# Driveunit_RS485_Topsheet.net
KiCad netlist of a schematic drawn in Altium Designer
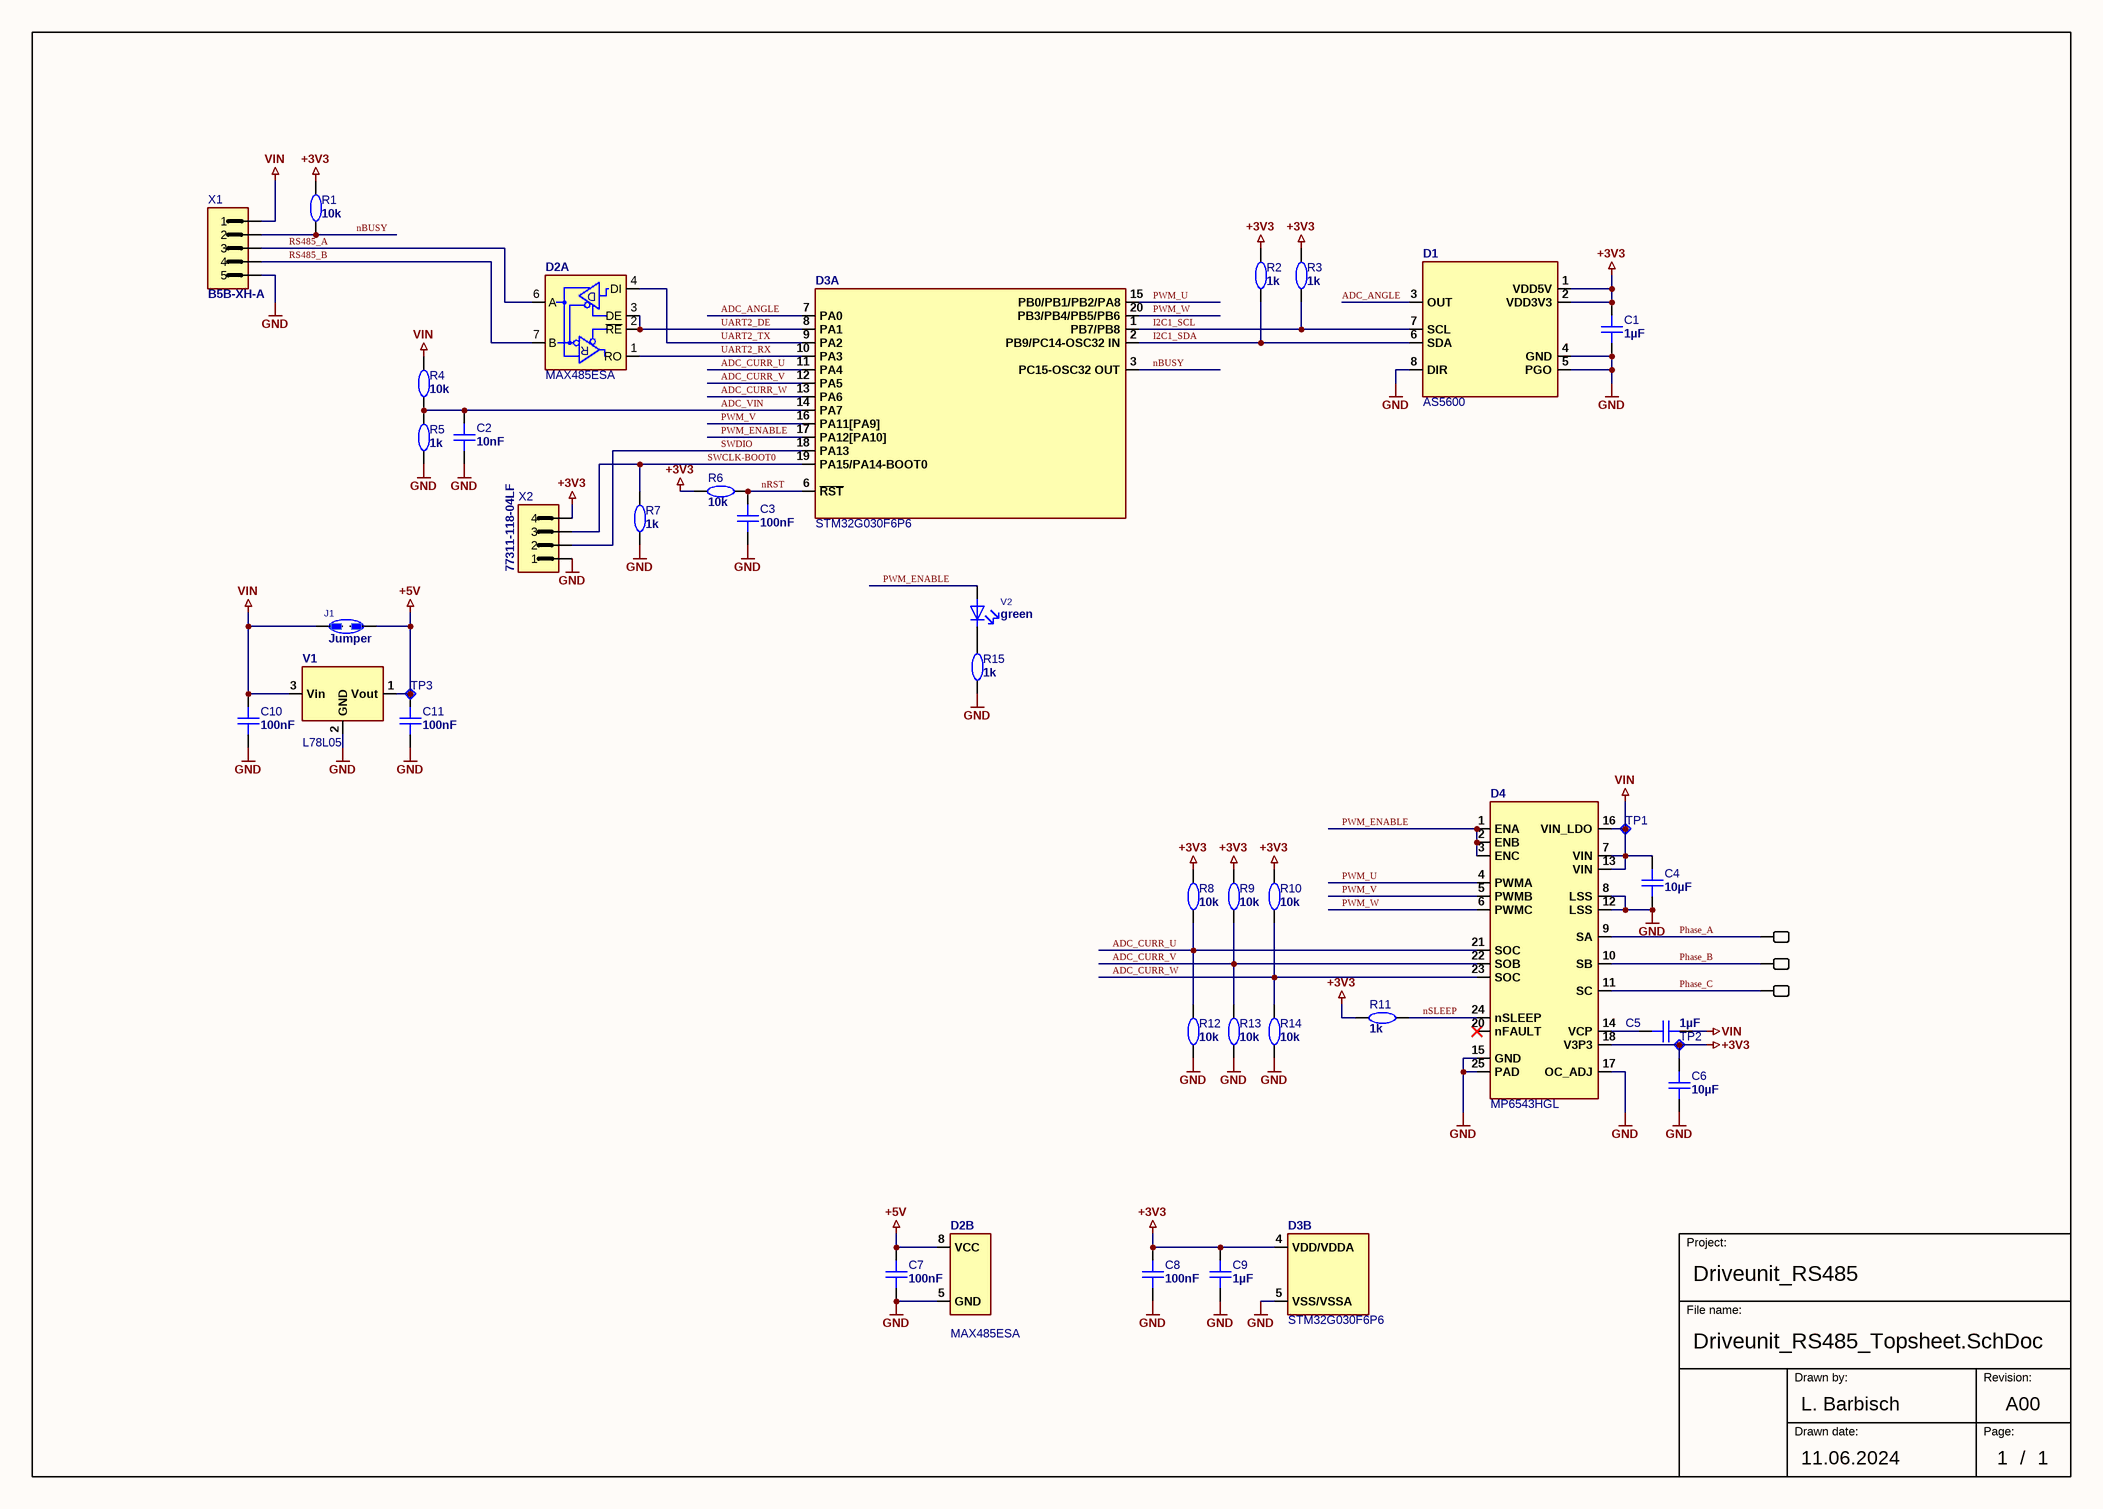
[diagram p0: Driveunit_RS485_Topsheet.SchDoc]

(export (version "E")
  (design (tool "Eeschema 10.0.6"))
  (components
    (comp (ref "C1")
      (value "1µF")
      (footprint "C-0603_1608_095_L_RF")
      (description "Cap Cer SMD 1u 16V 10% 0603 X7R")
      (fields
        (field (name "MANUFACTURER PART NUMBER") "0603YC105KAT2A")
        (field (name "MANUFACTURER") "AVX")
        (field (name "USER") "epph")
      )
      (libsource (lib "GPV Switzerland SA") (part "CAP"))
    )
    (comp (ref "C2")
      (value "10nF")
      (footprint "C-0603_1608_095_L_RF")
      (description "Cap Cer SMD 10n 50V 10% 0603 X7R")
      (fields
        (field (name "MANUFACTURER") "AVX")
        (field (name "MANUFACTURER PART NUMBER") "06035C103KAT")
        (field (name "USER") "epph")
      )
      (libsource (lib "GPV Switzerland SA") (part "CAP"))
    )
    (comp (ref "C3")
      (value "100nF")
      (footprint "C-0603_1608_095_L_RF")
      (description "Cap Cer SMD 100n 100V 10% 0603 X7R")
      (fields
        (field (name "MANUFACTURER PART NUMBER") "GRM188R72A104KA35")
        (field (name "MANUFACTURER") "MURATA")
        (field (name "USER") "zupa")
      )
      (libsource (lib "GPV Switzerland SA") (part "CAP"))
    )
    (comp (ref "C4")
      (value "10µF")
      (footprint "C-1210_3225_230_L_RF")
      (description "CAP CER 10uF 50V X7S 1210")
      (fields
        (field (name "MANUFACTURER") "TDK")
        (field (name "MANUFACTURER PART NUMBER") "C3225X7S1H106K250AE")
        (field (name "USER") "zupa")
      )
      (libsource (lib "GPV Switzerland SA") (part "CAP"))
    )
    (comp (ref "C5")
      (value "1µF")
      (footprint "C-0603_1608_095_L_RF")
      (description "Cap Cer SMD 1u 16V 10% 0603 X7R")
      (fields
        (field (name "MANUFACTURER PART NUMBER") "0603YC105KAT2A")
        (field (name "MANUFACTURER") "AVX")
        (field (name "USER") "epph")
      )
      (libsource (lib "GPV Switzerland SA") (part "CAP"))
    )
    (comp (ref "C6")
      (value "10µF")
      (footprint "C-0805_2012_145_L_RF")
      (description "Cap Cer SMD 10u 16V 10% 0805 X5R")
      (fields
        (field (name "MANUFACTURER PART NUMBER") "0805YD106KAT2A")
        (field (name "MANUFACTURER") "AVX")
        (field (name "USER") "zupa")
      )
      (libsource (lib "GPV Switzerland SA") (part "CAP"))
    )
    (comp (ref "C7")
      (value "100nF")
      (footprint "C-0603_1608_095_L_RF")
      (description "Cap Cer SMD 100n 100V 10% 0603 X7R")
      (fields
        (field (name "MANUFACTURER PART NUMBER") "GRM188R72A104KA35")
        (field (name "MANUFACTURER") "MURATA")
        (field (name "USER") "zupa")
      )
      (libsource (lib "GPV Switzerland SA") (part "CAP"))
    )
    (comp (ref "C8")
      (value "100nF")
      (footprint "C-0603_1608_095_L_RF")
      (description "Cap Cer SMD 100n 100V 10% 0603 X7R")
      (fields
        (field (name "MANUFACTURER PART NUMBER") "GRM188R72A104KA35")
        (field (name "MANUFACTURER") "MURATA")
        (field (name "USER") "zupa")
      )
      (libsource (lib "GPV Switzerland SA") (part "CAP"))
    )
    (comp (ref "C9")
      (value "1µF")
      (footprint "C-0603_1608_095_L_RF")
      (description "Cap Cer SMD 1u 16V 10% 0603 X7R")
      (fields
        (field (name "MANUFACTURER PART NUMBER") "0603YC105KAT2A")
        (field (name "MANUFACTURER") "AVX")
        (field (name "USER") "epph")
      )
      (libsource (lib "GPV Switzerland SA") (part "CAP"))
    )
    (comp (ref "C10")
      (value "100nF")
      (footprint "C-0603_1608_095_L_RF")
      (description "Cap Cer SMD 100n 100V 10% 0603 X7R")
      (fields
        (field (name "MANUFACTURER PART NUMBER") "GRM188R72A104KA35")
        (field (name "MANUFACTURER") "MURATA")
        (field (name "USER") "zupa")
      )
      (libsource (lib "GPV Switzerland SA") (part "CAP"))
    )
    (comp (ref "C11")
      (value "100nF")
      (footprint "C-0603_1608_095_L_RF")
      (description "Cap Cer SMD 100n 100V 10% 0603 X7R")
      (fields
        (field (name "MANUFACTURER PART NUMBER") "GRM188R72A104KA35")
        (field (name "MANUFACTURER") "MURATA")
        (field (name "USER") "zupa")
      )
      (libsource (lib "GPV Switzerland SA") (part "CAP"))
    )
    (comp (ref "D1")
      (value "AS5600")
      (footprint "SOIC8_N_RF")
      (description "IC Sensor Rotation Magnet 12bit")
      (fields (field (name "MANUFACTURER") "AMS"))
      (libsource (lib "Global Library") (part "AS5600"))
    )
    (comp (ref "D2")
      (value "MAX485ESA")
      (footprint "SOIC8_N_RF")
      (description "IC Transceiver RS485 5V")
      (fields (field (name "MANUFACTURER") "Maxim"))
      (libsource (lib "") (part "MAX485ESA_1"))
    )
    (comp (ref "D3")
      (value "STM32G030F6P6")
      (footprint "TSSOP20_N_RF")
      (description "IC MCU Cortex M0+ 32K Flash, 8K RAM, 64MHz")
      (fields (field (name "MANUFACTURER") "ST"))
      (libsource (lib "Global Library") (part "STM32G030F6P6"))
    )
    (comp (ref "D4")
      (value "MP6543HGL")
      (footprint "QFN24_5x7_N_RF")
      (description "Motor Driver 3-Phase 3-22V 2A")
      (fields
        (field (name "MANUFACTURER") "Monolithic Power Systems")
        (field (name "MANUFACTURER PART NUMBER") "MP6543HGL-A-P")
      )
      (libsource (lib "Global Library") (part "MP6543HGL-A-P"))
    )
    (comp (ref "J1")
      (value "Jumper")
      (footprint "J-1206_Solderjumper_2Pin")
      (description "Solder jumper 2Pin")
      (fields (field (name "USER") "epph"))
      (libsource (lib "GPV Switzerland SA") (part "Solder jumper 2Pin"))
    )
    (comp (ref "R1")
      (value "10k")
      (footprint "R-0603_1608_050_L_RF")
      (description "Res SMD 10k 1% 0.1W 0603")
      (fields
        (field (name "MANUFACTURER") "YAGEO")
        (field (name "MANUFACTURER PART NUMBER") "RC0603FR-0710KL")
        (field (name "USER") "zupa")
      )
      (libsource (lib "GPV Switzerland SA") (part "RES"))
    )
    (comp (ref "R2")
      (value "1k")
      (footprint "R-0603_1608_050_L_RF")
      (description "Res SMD 1k 1% 0.1W 0603")
      (fields
        (field (name "MANUFACTURER") "YAGEO")
        (field (name "MANUFACTURER PART NUMBER") "RC0603FR-071KL")
        (field (name "USER") "zupa")
      )
      (libsource (lib "GPV Switzerland SA") (part "RES"))
    )
    (comp (ref "R3")
      (value "1k")
      (footprint "R-0603_1608_050_L_RF")
      (description "Res SMD 1k 1% 0.1W 0603")
      (fields
        (field (name "MANUFACTURER") "YAGEO")
        (field (name "MANUFACTURER PART NUMBER") "RC0603FR-071KL")
        (field (name "USER") "zupa")
      )
      (libsource (lib "GPV Switzerland SA") (part "RES"))
    )
    (comp (ref "R4")
      (value "10k")
      (footprint "R-0603_1608_050_L_RF")
      (description "Res SMD 10k 1% 0.1W 0603")
      (fields
        (field (name "MANUFACTURER") "YAGEO")
        (field (name "MANUFACTURER PART NUMBER") "RC0603FR-0710KL")
        (field (name "USER") "zupa")
      )
      (libsource (lib "GPV Switzerland SA") (part "RES"))
    )
    (comp (ref "R5")
      (value "1k")
      (footprint "R-0603_1608_050_L_RF")
      (description "Res SMD 1k 1% 0.1W 0603")
      (fields
        (field (name "MANUFACTURER") "YAGEO")
        (field (name "MANUFACTURER PART NUMBER") "RC0603FR-071KL")
        (field (name "USER") "zupa")
      )
      (libsource (lib "GPV Switzerland SA") (part "RES"))
    )
    (comp (ref "R6")
      (value "10k")
      (footprint "R-0603_1608_050_L_RF")
      (description "Res SMD 10k 1% 0.1W 0603")
      (fields
        (field (name "MANUFACTURER") "YAGEO")
        (field (name "MANUFACTURER PART NUMBER") "RC0603FR-0710KL")
        (field (name "USER") "zupa")
      )
      (libsource (lib "GPV Switzerland SA") (part "RES"))
    )
    (comp (ref "R7")
      (value "1k")
      (footprint "R-0603_1608_050_L_RF")
      (description "Res SMD 1k 1% 0.1W 0603")
      (fields
        (field (name "MANUFACTURER") "YAGEO")
        (field (name "MANUFACTURER PART NUMBER") "RC0603FR-071KL")
        (field (name "USER") "zupa")
      )
      (libsource (lib "GPV Switzerland SA") (part "RES"))
    )
    (comp (ref "R8")
      (value "10k")
      (footprint "R-0603_1608_050_L_RF")
      (description "Res SMD 10k 1% 0.1W 0603")
      (fields
        (field (name "MANUFACTURER") "YAGEO")
        (field (name "MANUFACTURER PART NUMBER") "RC0603FR-0710KL")
        (field (name "USER") "zupa")
      )
      (libsource (lib "GPV Switzerland SA") (part "RES"))
    )
    (comp (ref "R9")
      (value "10k")
      (footprint "R-0603_1608_050_L_RF")
      (description "Res SMD 10k 1% 0.1W 0603")
      (fields
        (field (name "MANUFACTURER") "YAGEO")
        (field (name "MANUFACTURER PART NUMBER") "RC0603FR-0710KL")
        (field (name "USER") "zupa")
      )
      (libsource (lib "GPV Switzerland SA") (part "RES"))
    )
    (comp (ref "R10")
      (value "10k")
      (footprint "R-0603_1608_050_L_RF")
      (description "Res SMD 10k 1% 0.1W 0603")
      (fields
        (field (name "MANUFACTURER") "YAGEO")
        (field (name "MANUFACTURER PART NUMBER") "RC0603FR-0710KL")
        (field (name "USER") "zupa")
      )
      (libsource (lib "GPV Switzerland SA") (part "RES"))
    )
    (comp (ref "R11")
      (value "1k")
      (footprint "R-0603_1608_050_L_RF")
      (description "Res SMD 1k 1% 0.1W 0603")
      (fields
        (field (name "MANUFACTURER") "YAGEO")
        (field (name "MANUFACTURER PART NUMBER") "RC0603FR-071KL")
        (field (name "USER") "zupa")
      )
      (libsource (lib "GPV Switzerland SA") (part "RES"))
    )
    (comp (ref "R12")
      (value "10k")
      (footprint "R-0603_1608_050_L_RF")
      (description "Res SMD 10k 1% 0.1W 0603")
      (fields
        (field (name "MANUFACTURER") "YAGEO")
        (field (name "MANUFACTURER PART NUMBER") "RC0603FR-0710KL")
        (field (name "USER") "zupa")
      )
      (libsource (lib "GPV Switzerland SA") (part "RES"))
    )
    (comp (ref "R13")
      (value "10k")
      (footprint "R-0603_1608_050_L_RF")
      (description "Res SMD 10k 1% 0.1W 0603")
      (fields
        (field (name "MANUFACTURER") "YAGEO")
        (field (name "MANUFACTURER PART NUMBER") "RC0603FR-0710KL")
        (field (name "USER") "zupa")
      )
      (libsource (lib "GPV Switzerland SA") (part "RES"))
    )
    (comp (ref "R14")
      (value "10k")
      (footprint "R-0603_1608_050_L_RF")
      (description "Res SMD 10k 1% 0.1W 0603")
      (fields
        (field (name "MANUFACTURER") "YAGEO")
        (field (name "MANUFACTURER PART NUMBER") "RC0603FR-0710KL")
        (field (name "USER") "zupa")
      )
      (libsource (lib "GPV Switzerland SA") (part "RES"))
    )
    (comp (ref "R15")
      (value "1k")
      (footprint "R-0603_1608_050_L_RF")
      (description "Res SMD 1k 1% 0.1W 0603")
      (fields
        (field (name "MANUFACTURER") "YAGEO")
        (field (name "MANUFACTURER PART NUMBER") "RC0603FR-071KL")
        (field (name "USER") "zupa")
      )
      (libsource (lib "GPV Switzerland SA") (part "RES"))
    )
    (comp (ref "TP1")
      (value "TestPoint 0.8mm")
      (footprint "TP_0.8mm")
      (fields (field (name "USER") "zupa"))
      (libsource (lib "GPV Switzerland SA") (part "Testpoint"))
    )
    (comp (ref "TP2")
      (value "TestPoint 0.8mm")
      (footprint "TP_0.8mm")
      (fields (field (name "USER") "zupa"))
      (libsource (lib "GPV Switzerland SA") (part "Testpoint"))
    )
    (comp (ref "TP3")
      (value "TestPoint 0.8mm")
      (footprint "TP_0.8mm")
      (fields (field (name "USER") "zupa"))
      (libsource (lib "GPV Switzerland SA") (part "Testpoint"))
    )
    (comp (ref "V1")
      (value "L78L05")
      (footprint "SOT-89-3")
      (description "IC REG 5V SOT-89-3 7-30V 100mA")
      (fields (field (name "MANUFACTURER") "ST"))
      (libsource (lib "Global Library") (part "L78L05"))
    )
    (comp (ref "V2")
      (value "green")
      (footprint "LED-0603_1608_Green_L_RF")
      (description "LED Green LTST-C190KGKT 0603")
      (fields
        (field (name "MANUFACTURER") "Lite-On Inc")
        (field (name "MANUFACTURER PART NUMBER") "LTST-C190KGKT")
        (field (name "USER") "epph")
      )
      (libsource (lib "GPV Switzerland SA") (part "LED"))
    )
    (comp (ref "X1")
      (value "B5B-XH-A")
      (footprint "X-0149X0057-R_M05_P0250_JST_B5B-XH-A")
      (description "CONN HEADER  5POS_JST_B5B-XH")
      (fields
        (field (name "MANUFACTURER") "JST")
        (field (name "Comment") "CONN HEADER XH 5POS THT")
        (field (name "USER") "balu")
      )
      (libsource (lib "GPV Switzerland SA") (part "Connector-5P"))
    )
    (comp (ref "X2")
      (value "77311-118-04LF")
      (footprint "X-0101X0025_R_FCI_77311-118-04LF")
      (description "CONN HEADER 4POS 1ROW THT 2.54MM FCI 77311-118-04LF")
      (fields
        (field (name "MANUFACTURER") "FCI")
        (field (name "Comment") "CONN HEADER 4POS 1ROW THT 2.54MM")
        (field (name "USER") "zupa")
      )
      (libsource (lib "GPV Switzerland SA") (part "Connector-4P"))
    )
    (comp (ref "X3")
      (value "Solderpad_2x3")
      (footprint "Lötpad_2x3")
      (description "Solderpad 2mm x 3mm")
      (libsource (lib "Global Library") (part "Lötpad_2mmx3mm"))
    )
    (comp (ref "X4")
      (value "Solderpad_2x3")
      (footprint "Lötpad_2x3")
      (description "Solderpad 2mm x 3mm")
      (libsource (lib "Global Library") (part "Lötpad_2mmx3mm"))
    )
    (comp (ref "X5")
      (value "Solderpad_2x3")
      (footprint "Lötpad_2x3")
      (description "Solderpad 2mm x 3mm")
      (libsource (lib "Global Library") (part "Lötpad_2mmx3mm"))
    )
  )
  (nets
    (net (code "1") (name "+3V3") (class "Default")
      (node (ref "C1") (pin "2") (pinfunction "2_2") (pintype "passive"))
      (node (ref "C6") (pin "2") (pinfunction "2_2") (pintype "passive"))
      (node (ref "C8") (pin "2") (pinfunction "2_2") (pintype "passive"))
      (node (ref "C9") (pin "2") (pinfunction "2_2") (pintype "passive"))
      (node (ref "D1") (pin "1") (pinfunction "VDD5V_1") (pintype "passive"))
      (node (ref "D1") (pin "2") (pinfunction "VDD3V3_2") (pintype "passive"))
      (node (ref "D3") (pin "4") (pinfunction "VDD/VDDA_4") (pintype "passive"))
      (node (ref "D4") (pin "18") (pinfunction "V3P3_18") (pintype "passive"))
      (node (ref "R1") (pin "2") (pinfunction "2_2") (pintype "passive"))
      (node (ref "R10") (pin "2") (pinfunction "2_2") (pintype "passive"))
      (node (ref "R11") (pin "2") (pinfunction "2_2") (pintype "passive"))
      (node (ref "R2") (pin "2") (pinfunction "2_2") (pintype "passive"))
      (node (ref "R3") (pin "2") (pinfunction "2_2") (pintype "passive"))
      (node (ref "R6") (pin "1") (pinfunction "1_1") (pintype "passive"))
      (node (ref "R8") (pin "2") (pinfunction "2_2") (pintype "passive"))
      (node (ref "R9") (pin "2") (pinfunction "2_2") (pintype "passive"))
      (node (ref "TP2") (pin "1") (pinfunction "1_1") (pintype "passive"))
      (node (ref "X2") (pin "4") (pinfunction "4_4") (pintype "passive"))
    )
    (net (code "2") (name "+5V") (class "Default")
      (node (ref "C11") (pin "2") (pinfunction "2_2") (pintype "passive"))
      (node (ref "C7") (pin "2") (pinfunction "2_2") (pintype "passive"))
      (node (ref "D2") (pin "8") (pinfunction "VCC_8") (pintype "passive"))
      (node (ref "J1") (pin "2") (pinfunction "2_2") (pintype "passive"))
      (node (ref "TP3") (pin "1") (pinfunction "1_1") (pintype "passive"))
      (node (ref "V1") (pin "1") (pinfunction "Vout_1") (pintype "passive"))
    )
    (net (code "3") (name "/ADC_ANGLE") (class "Default")
      (node (ref "D1") (pin "3") (pinfunction "OUT_3") (pintype "passive"))
      (node (ref "D3") (pin "7") (pinfunction "PA0_7") (pintype "passive"))
    )
    (net (code "4") (name "/ADC_CURR_U") (class "Default")
      (node (ref "D3") (pin "11") (pinfunction "PA4_11") (pintype "passive"))
      (node (ref "D4") (pin "21") (pinfunction "SOC_21") (pintype "passive"))
      (node (ref "R12") (pin "2") (pinfunction "2_2") (pintype "passive"))
      (node (ref "R8") (pin "1") (pinfunction "1_1") (pintype "passive"))
    )
    (net (code "5") (name "/ADC_CURR_V") (class "Default")
      (node (ref "D3") (pin "12") (pinfunction "PA5_12") (pintype "passive"))
      (node (ref "D4") (pin "22") (pinfunction "SOB_22") (pintype "passive"))
      (node (ref "R13") (pin "2") (pinfunction "2_2") (pintype "passive"))
      (node (ref "R9") (pin "1") (pinfunction "1_1") (pintype "passive"))
    )
    (net (code "6") (name "/ADC_CURR_W") (class "Default")
      (node (ref "D3") (pin "13") (pinfunction "PA6_13") (pintype "passive"))
      (node (ref "D4") (pin "23") (pinfunction "SOC_23") (pintype "passive"))
      (node (ref "R10") (pin "1") (pinfunction "1_1") (pintype "passive"))
      (node (ref "R14") (pin "2") (pinfunction "2_2") (pintype "passive"))
    )
    (net (code "7") (name "/ADC_VIN") (class "Default")
      (node (ref "C2") (pin "2") (pinfunction "2_2") (pintype "passive"))
      (node (ref "D3") (pin "14") (pinfunction "PA7_14") (pintype "passive"))
      (node (ref "R4") (pin "1") (pinfunction "1_1") (pintype "passive"))
      (node (ref "R5") (pin "2") (pinfunction "2_2") (pintype "passive"))
    )
    (net (code "8") (name "/I2C1_SCL") (class "Default")
      (node (ref "D1") (pin "7") (pinfunction "SCL_7") (pintype "passive"))
      (node (ref "D3") (pin "1") (pinfunction "PB7/PB8_1") (pintype "passive"))
      (node (ref "R3") (pin "1") (pinfunction "1_1") (pintype "passive"))
    )
    (net (code "9") (name "/I2C1_SDA") (class "Default")
      (node (ref "D1") (pin "6") (pinfunction "SDA_6") (pintype "passive"))
      (node (ref "D3") (pin "2") (pinfunction "PB9/PC14-OSC32_IN_2") (pintype "passive"))
      (node (ref "R2") (pin "1") (pinfunction "1_1") (pintype "passive"))
    )
    (net (code "10") (name "/PWM_ENABLE") (class "Default")
      (node (ref "D3") (pin "17") (pinfunction "PA12[PA10]_17") (pintype "passive"))
      (node (ref "D4") (pin "1") (pinfunction "ENA_1") (pintype "passive"))
      (node (ref "D4") (pin "2") (pinfunction "ENB_2") (pintype "passive"))
      (node (ref "D4") (pin "3") (pinfunction "ENC_3") (pintype "passive"))
      (node (ref "V2") (pin "1") (pinfunction "1_1") (pintype "passive"))
    )
    (net (code "11") (name "/PWM_U") (class "Default")
      (node (ref "D3") (pin "15") (pinfunction "PB0/PB1/PB2/PA8_15") (pintype "passive"))
      (node (ref "D4") (pin "4") (pinfunction "PWMA_4") (pintype "passive"))
    )
    (net (code "12") (name "/PWM_V") (class "Default")
      (node (ref "D3") (pin "16") (pinfunction "PA11[PA9]_16") (pintype "passive"))
      (node (ref "D4") (pin "5") (pinfunction "PWMB_5") (pintype "passive"))
    )
    (net (code "13") (name "/PWM_W") (class "Default")
      (node (ref "D3") (pin "20") (pinfunction "PB3/PB4/PB5/PB6_20") (pintype "passive"))
      (node (ref "D4") (pin "6") (pinfunction "PWMC_6") (pintype "passive"))
    )
    (net (code "14") (name "/Phase_A") (class "Default")
      (node (ref "D4") (pin "9") (pinfunction "SA_9") (pintype "passive"))
      (node (ref "X3") (pin "1") (pintype "passive"))
    )
    (net (code "15") (name "/Phase_B") (class "Default")
      (node (ref "D4") (pin "10") (pinfunction "SB_10") (pintype "passive"))
      (node (ref "X4") (pin "1") (pintype "passive"))
    )
    (net (code "16") (name "/Phase_C") (class "Default")
      (node (ref "D4") (pin "11") (pinfunction "SC_11") (pintype "passive"))
      (node (ref "X5") (pin "1") (pintype "passive"))
    )
    (net (code "17") (name "/RS485_A") (class "Default")
      (node (ref "D2") (pin "6") (pinfunction "A_6") (pintype "passive"))
      (node (ref "X1") (pin "3") (pinfunction "3_3") (pintype "passive"))
    )
    (net (code "18") (name "/RS485_B") (class "Default")
      (node (ref "D2") (pin "7") (pinfunction "B_7") (pintype "passive"))
      (node (ref "X1") (pin "4") (pinfunction "4_4") (pintype "passive"))
    )
    (net (code "19") (name "/SWCLK-BOOT0") (class "Default")
      (node (ref "D3") (pin "19") (pinfunction "PA15/PA14-BOOT0_19") (pintype "passive"))
      (node (ref "R7") (pin "2") (pinfunction "2_2") (pintype "passive"))
      (node (ref "X2") (pin "3") (pinfunction "3_3") (pintype "passive"))
    )
    (net (code "20") (name "/SWDIO") (class "Default")
      (node (ref "D3") (pin "18") (pinfunction "PA13_18") (pintype "passive"))
      (node (ref "X2") (pin "2") (pinfunction "2_2") (pintype "passive"))
    )
    (net (code "21") (name "/UART2_DE") (class "Default")
      (node (ref "D2") (pin "2") (pinfunction "~{RE}_2") (pintype "passive"))
      (node (ref "D2") (pin "3") (pinfunction "DE_3") (pintype "passive"))
      (node (ref "D3") (pin "8") (pinfunction "PA1_8") (pintype "passive"))
    )
    (net (code "22") (name "/UART2_RX") (class "Default")
      (node (ref "D2") (pin "1") (pinfunction "RO_1") (pintype "passive"))
      (node (ref "D3") (pin "10") (pinfunction "PA3_10") (pintype "passive"))
    )
    (net (code "23") (name "/UART2_TX") (class "Default")
      (node (ref "D2") (pin "4") (pinfunction "DI_4") (pintype "passive"))
      (node (ref "D3") (pin "9") (pinfunction "PA2_9") (pintype "passive"))
    )
    (net (code "24") (name "/nBUSY") (class "Default")
      (node (ref "D3") (pin "3") (pinfunction "PC15-OSC32_OUT_3") (pintype "passive"))
      (node (ref "R1") (pin "1") (pinfunction "1_1") (pintype "passive"))
      (node (ref "X1") (pin "2") (pinfunction "2_2") (pintype "passive"))
    )
    (net (code "25") (name "/nRST") (class "Default")
      (node (ref "C3") (pin "2") (pinfunction "2_2") (pintype "passive"))
      (node (ref "D3") (pin "6") (pinfunction "~{RST}_6") (pintype "passive"))
      (node (ref "R6") (pin "2") (pinfunction "2_2") (pintype "passive"))
    )
    (net (code "26") (name "/nSLEEP") (class "Default")
      (node (ref "D4") (pin "24") (pinfunction "nSLEEP_24") (pintype "passive"))
      (node (ref "R11") (pin "1") (pinfunction "1_1") (pintype "passive"))
    )
    (net (code "27") (name "GND") (class "Default")
      (node (ref "C1") (pin "1") (pinfunction "1_1") (pintype "passive"))
      (node (ref "C10") (pin "1") (pinfunction "1_1") (pintype "passive"))
      (node (ref "C11") (pin "1") (pinfunction "1_1") (pintype "passive"))
      (node (ref "C2") (pin "1") (pinfunction "1_1") (pintype "passive"))
      (node (ref "C3") (pin "1") (pinfunction "1_1") (pintype "passive"))
      (node (ref "C4") (pin "1") (pinfunction "1_1") (pintype "passive"))
      (node (ref "C6") (pin "1") (pinfunction "1_1") (pintype "passive"))
      (node (ref "C7") (pin "1") (pinfunction "1_1") (pintype "passive"))
      (node (ref "C8") (pin "1") (pinfunction "1_1") (pintype "passive"))
      (node (ref "C9") (pin "1") (pinfunction "1_1") (pintype "passive"))
      (node (ref "D1") (pin "4") (pinfunction "GND_4") (pintype "passive"))
      (node (ref "D1") (pin "5") (pinfunction "PGO_5") (pintype "passive"))
      (node (ref "D1") (pin "8") (pinfunction "DIR_8") (pintype "passive"))
      (node (ref "D2") (pin "5") (pinfunction "GND_5") (pintype "passive"))
      (node (ref "D3") (pin "5") (pinfunction "VSS/VSSA_5") (pintype "passive"))
      (node (ref "D4") (pin "12") (pinfunction "LSS_12") (pintype "passive"))
      (node (ref "D4") (pin "15") (pinfunction "GND_15") (pintype "passive"))
      (node (ref "D4") (pin "17") (pinfunction "OC_ADJ_17") (pintype "passive"))
      (node (ref "D4") (pin "25") (pinfunction "PAD_25") (pintype "passive"))
      (node (ref "D4") (pin "8") (pinfunction "LSS_8") (pintype "passive"))
      (node (ref "R12") (pin "1") (pinfunction "1_1") (pintype "passive"))
      (node (ref "R13") (pin "1") (pinfunction "1_1") (pintype "passive"))
      (node (ref "R14") (pin "1") (pinfunction "1_1") (pintype "passive"))
      (node (ref "R15") (pin "1") (pinfunction "1_1") (pintype "passive"))
      (node (ref "R5") (pin "1") (pinfunction "1_1") (pintype "passive"))
      (node (ref "R7") (pin "1") (pinfunction "1_1") (pintype "passive"))
      (node (ref "V1") (pin "2") (pinfunction "GND_2") (pintype "passive"))
      (node (ref "X1") (pin "5") (pinfunction "5_5") (pintype "passive"))
      (node (ref "X2") (pin "1") (pinfunction "1_1") (pintype "passive"))
    )
    (net (code "28") (name "Net-(D4-VCP)") (class "Default")
      (node (ref "C5") (pin "1") (pinfunction "1_1") (pintype "passive"))
      (node (ref "D4") (pin "14") (pinfunction "VCP_14") (pintype "passive"))
    )
    (net (code "29") (name "Net-(R15-Pad2)") (class "Default")
      (node (ref "R15") (pin "2") (pinfunction "2_2") (pintype "passive"))
      (node (ref "V2") (pin "2") (pinfunction "2_2") (pintype "passive"))
    )
    (net (code "30") (name "VIN") (class "Default")
      (node (ref "C10") (pin "2") (pinfunction "2_2") (pintype "passive"))
      (node (ref "C4") (pin "2") (pinfunction "2_2") (pintype "passive"))
      (node (ref "C5") (pin "2") (pinfunction "2_2") (pintype "passive"))
      (node (ref "D4") (pin "13") (pinfunction "VIN_13") (pintype "passive"))
      (node (ref "D4") (pin "16") (pinfunction "VIN_LDO_16") (pintype "passive"))
      (node (ref "D4") (pin "7") (pinfunction "VIN_7") (pintype "passive"))
      (node (ref "J1") (pin "1") (pinfunction "1_1") (pintype "passive"))
      (node (ref "R4") (pin "2") (pinfunction "2_2") (pintype "passive"))
      (node (ref "TP1") (pin "1") (pinfunction "1_1") (pintype "passive"))
      (node (ref "V1") (pin "3") (pinfunction "Vin_3") (pintype "passive"))
      (node (ref "X1") (pin "1") (pinfunction "1_1") (pintype "passive"))
    )
    (net (code "31") (name "unconnected-(D4-nFAULT-Pad20)") (class "Default")
      (node (ref "D4") (pin "20") (pinfunction "nFAULT_20") (pintype "passive+no_connect"))
    )
  )
)
